# mother_card_20.net
KiCad netlist of a schematic drawn in EAGLE
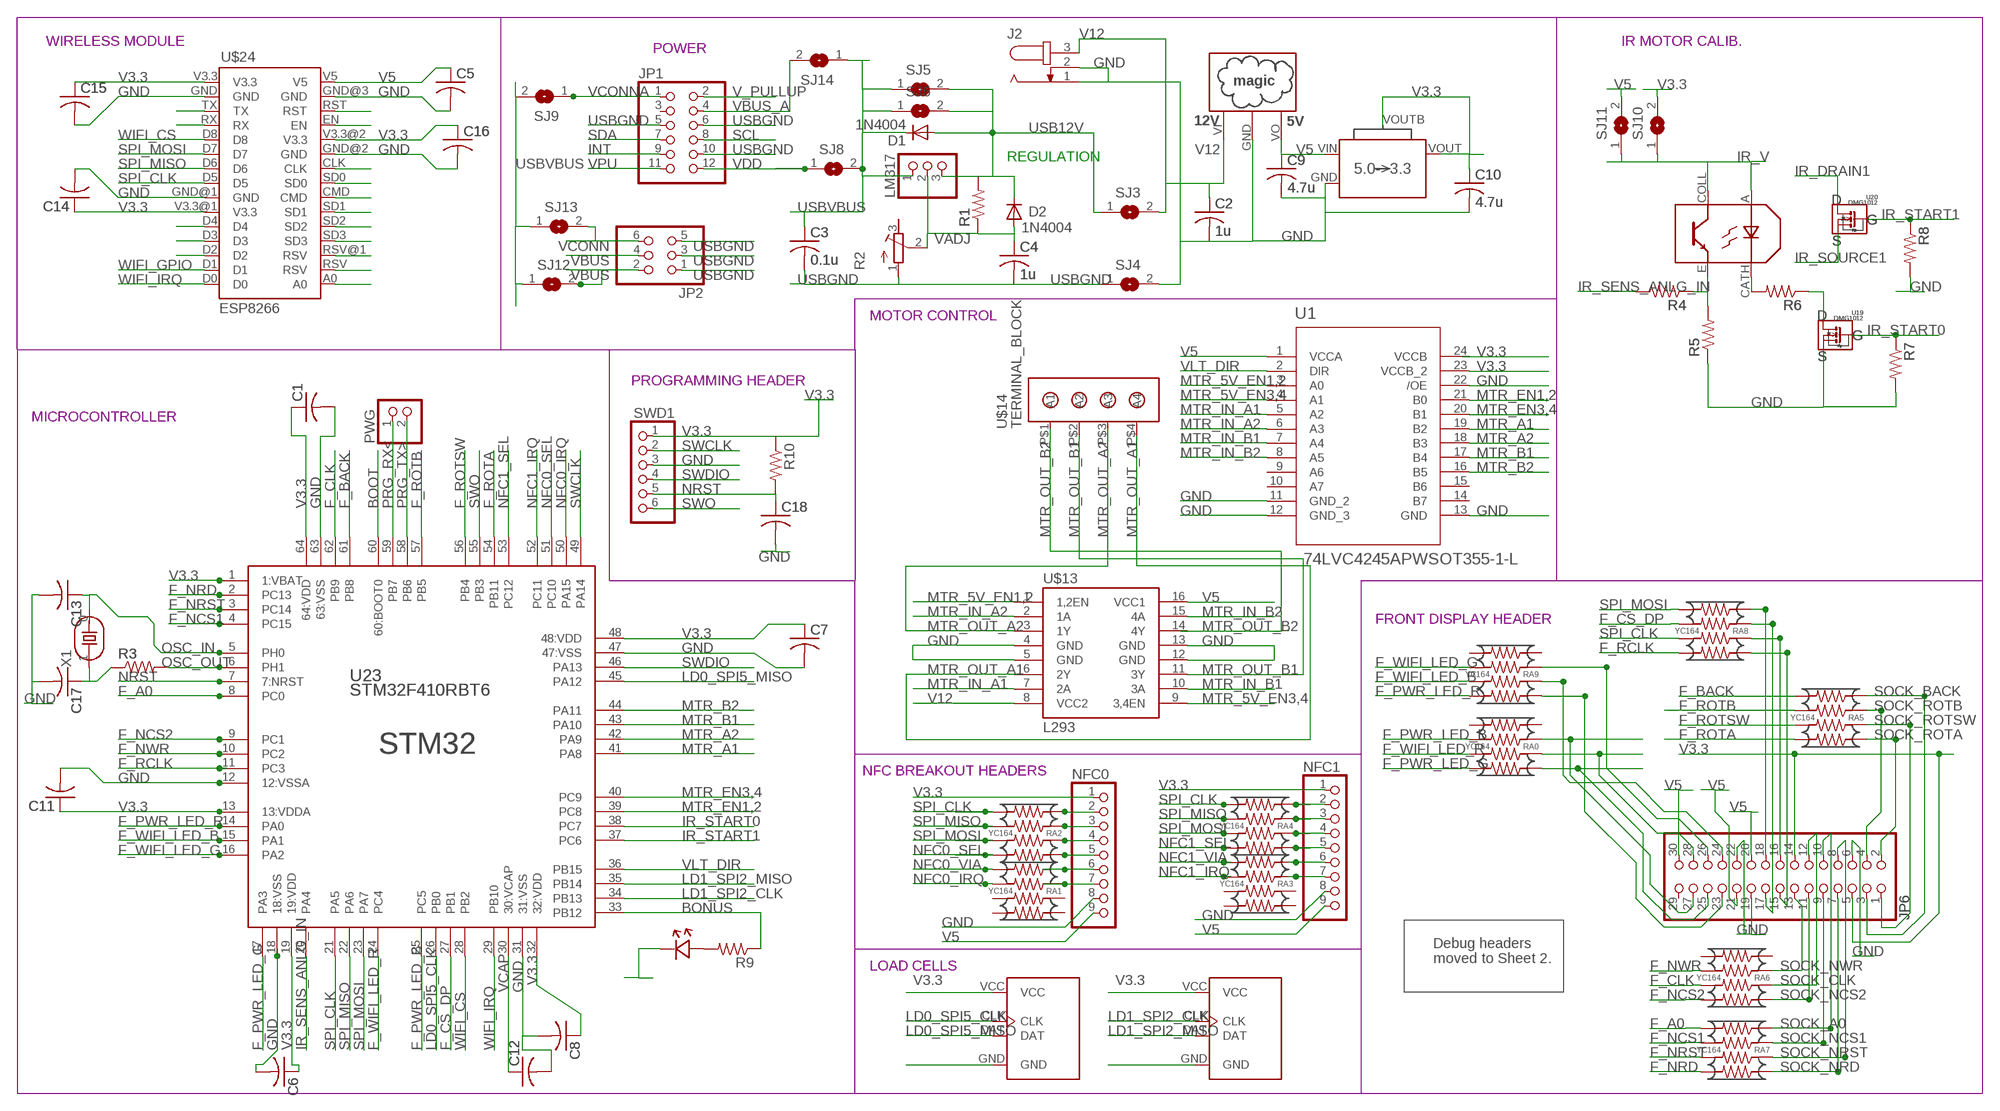
[diagram p0: schematic, sheet 1]
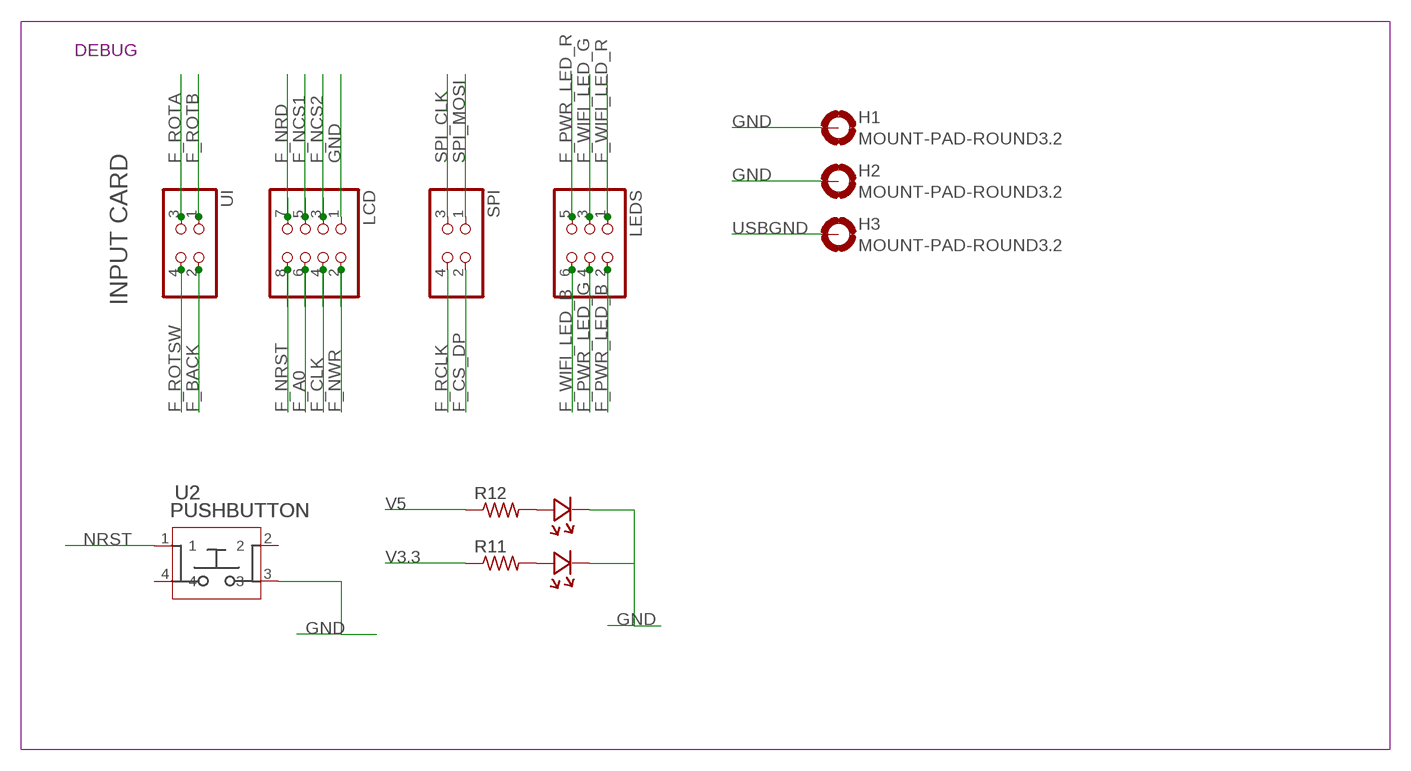
[diagram p1: schematic, sheet 2]

(export (version "E")
  (design (tool "Eeschema 10.0.6"))
  (components
    (comp (ref "H1")
      (value "MOUNT-PAD-ROUND3.2")
      (footprint "eagle-import:3,2-PAD")
      (libsource (lib "eagle-import") (part "MOUNT-PAD-ROUND3.2"))
    )
    (comp (ref "H2")
      (value "MOUNT-PAD-ROUND3.2")
      (footprint "eagle-import:3,2-PAD")
      (libsource (lib "eagle-import") (part "MOUNT-PAD-ROUND3.2"))
    )
    (comp (ref "H3")
      (value "MOUNT-PAD-ROUND3.2")
      (footprint "eagle-import:3,2-PAD")
      (libsource (lib "eagle-import") (part "MOUNT-PAD-ROUND3.2"))
    )
    (comp (ref "LCD")
      (value "PINHD-2X4")
      (footprint "eagle-import:2X04")
      (libsource (lib "eagle-import") (part "PINHD-2X4"))
    )
    (comp (ref "LEDS")
      (value "PINHD-2X3")
      (footprint "eagle-import:2X03")
      (libsource (lib "eagle-import") (part "PINHD-2X3"))
    )
    (comp (ref "R11")
      (value "R-US_R0805")
      (footprint "eagle-import:R0805")
      (libsource (lib "eagle-import") (part "seniorDesign_R-US_R0805"))
    )
    (comp (ref "R12")
      (value "R-US_R0805")
      (footprint "eagle-import:R0805")
      (libsource (lib "eagle-import") (part "seniorDesign_R-US_R0805"))
    )
    (comp (ref "SPI")
      (value "PINHD-2X2")
      (footprint "eagle-import:2X02")
      (libsource (lib "eagle-import") (part "PINHD-2X2"))
    )
    (comp (ref "U$2")
      (value "LED0603")
      (footprint "eagle-import:LED")
      (libsource (lib "eagle-import") (part "LED0603"))
    )
    (comp (ref "U$3")
      (value "LED0603")
      (footprint "eagle-import:LED")
      (libsource (lib "eagle-import") (part "LED0603"))
    )
    (comp (ref "U2")
      (value "PUSHBUTTON")
      (footprint "eagle-import:SWITCH_FSM14JH")
      (fields (field (name "MANUFACTURER_PART_NUMBER") "218259107"))
      (libsource (lib "eagle-import") (part "PUSHBUTTON"))
    )
    (comp (ref "UI")
      (value "PINHD-2X2")
      (footprint "eagle-import:2X02")
      (libsource (lib "eagle-import") (part "PINHD-2X2"))
    )
    (comp (ref "C1")
      (value "C-USC0805")
      (footprint "eagle-import:C0805")
      (libsource (lib "eagle-import") (part "C-USC0805"))
    )
    (comp (ref "C2")
      (value "1u")
      (footprint "eagle-import:C0805")
      (libsource (lib "eagle-import") (part "C-USC0805"))
    )
    (comp (ref "C3")
      (value "0.1u")
      (footprint "eagle-import:C0805")
      (libsource (lib "eagle-import") (part "C-USC0805"))
    )
    (comp (ref "C4")
      (value "1u")
      (footprint "eagle-import:C0805")
      (libsource (lib "eagle-import") (part "C-USC0805"))
    )
    (comp (ref "C5")
      (value "C-USC0805")
      (footprint "eagle-import:C0805")
      (libsource (lib "eagle-import") (part "C-USC0805"))
    )
    (comp (ref "C6")
      (value "C-USC0805")
      (footprint "eagle-import:C0805")
      (libsource (lib "eagle-import") (part "C-USC0805"))
    )
    (comp (ref "C7")
      (value "C-USC0805")
      (footprint "eagle-import:C0805")
      (libsource (lib "eagle-import") (part "C-USC0805"))
    )
    (comp (ref "C8")
      (value "C-USC0805")
      (footprint "eagle-import:C0805")
      (libsource (lib "eagle-import") (part "C-USC0805"))
    )
    (comp (ref "C9")
      (value "4.7u")
      (footprint "eagle-import:C0805")
      (libsource (lib "eagle-import") (part "C-USC0805"))
    )
    (comp (ref "C10")
      (value "4.7u")
      (footprint "eagle-import:C0805")
      (libsource (lib "eagle-import") (part "C-USC0805"))
    )
    (comp (ref "C11")
      (value "C-USC0805")
      (footprint "eagle-import:C0805")
      (libsource (lib "eagle-import") (part "C-USC0805"))
    )
    (comp (ref "C12")
      (value "C-USC0805")
      (footprint "eagle-import:C0805")
      (libsource (lib "eagle-import") (part "C-USC0805"))
    )
    (comp (ref "C13")
      (value "C-USC0603")
      (footprint "eagle-import:C0603")
      (libsource (lib "eagle-import") (part "C-USC0603"))
    )
    (comp (ref "C14")
      (value "C-USC0805")
      (footprint "eagle-import:C0805")
      (libsource (lib "eagle-import") (part "C-USC0805"))
    )
    (comp (ref "C15")
      (value "C-USC0805")
      (footprint "eagle-import:C0805")
      (libsource (lib "eagle-import") (part "C-USC0805"))
    )
    (comp (ref "C16")
      (value "C-USC0805")
      (footprint "eagle-import:C0805")
      (libsource (lib "eagle-import") (part "C-USC0805"))
    )
    (comp (ref "C17")
      (value "C-USC0603")
      (footprint "eagle-import:C0603")
      (libsource (lib "eagle-import") (part "C-USC0603"))
    )
    (comp (ref "C18")
      (value "C-USC0805")
      (footprint "eagle-import:C0805")
      (libsource (lib "eagle-import") (part "C-USC0805"))
    )
    (comp (ref "D1")
      (value "1N4004")
      (footprint "eagle-import:DO41-10")
      (libsource (lib "eagle-import") (part "1N4004"))
    )
    (comp (ref "D2")
      (value "1N4004")
      (footprint "eagle-import:DO41-10")
      (libsource (lib "eagle-import") (part "1N4004"))
    )
    (comp (ref "IRSENS")
      (value "TCRT5000")
      (footprint "eagle-import:TCRT5000")
      (libsource (lib "eagle-import") (part "TCRT5000"))
    )
    (comp (ref "J2")
      (value "JACK-PLUG0")
      (footprint "eagle-import:SPC4077")
      (libsource (lib "eagle-import") (part "JACK-PLUG0"))
    )
    (comp (ref "JP1")
      (value "PINHD-2X6")
      (footprint "eagle-import:2X06")
      (libsource (lib "eagle-import") (part "PINHD-2X6"))
    )
    (comp (ref "JP2")
      (value "PINHD-2X3")
      (footprint "eagle-import:2X03")
      (libsource (lib "eagle-import") (part "PINHD-2X3"))
    )
    (comp (ref "JP6")
      (value "PINHD-2X15/SOCK")
      (footprint "eagle-import:2X15_SOCK")
      (libsource (lib "eagle-import") (part "PINHD-2X15/SOCK"))
    )
    (comp (ref "LM317")
      (value "PINHD-1X3")
      (footprint "eagle-import:1X03")
      (libsource (lib "eagle-import") (part "PINHD-1X3"))
    )
    (comp (ref "NFC0")
      (value "PINHD-1X9")
      (footprint "eagle-import:1X09")
      (libsource (lib "eagle-import") (part "PINHD-1X9"))
    )
    (comp (ref "NFC1")
      (value "PINHD-1X9")
      (footprint "eagle-import:1X09")
      (libsource (lib "eagle-import") (part "PINHD-1X9"))
    )
    (comp (ref "PWG")
      (value "PINHD-1X2")
      (footprint "eagle-import:1X02")
      (libsource (lib "eagle-import") (part "PINHD-1X2"))
    )
    (comp (ref "R1")
      (value "R-US_R0805")
      (footprint "eagle-import:R0805")
      (libsource (lib "eagle-import") (part "seniorDesign_R-US_R0805"))
    )
    (comp (ref "R2")
      (value "R-TRIMM64W")
      (footprint "eagle-import:RTRIM64W")
      (libsource (lib "eagle-import") (part "R-TRIMM64W"))
    )
    (comp (ref "R3")
      (value "R-US_R0805")
      (footprint "eagle-import:R0805")
      (libsource (lib "eagle-import") (part "seniorDesign_R-US_R0805"))
    )
    (comp (ref "R4")
      (value "R-US_R0805")
      (footprint "eagle-import:R0805")
      (libsource (lib "eagle-import") (part "seniorDesign_R-US_R0805"))
    )
    (comp (ref "R5")
      (value "R-US_R0805")
      (footprint "eagle-import:R0805")
      (libsource (lib "eagle-import") (part "seniorDesign_R-US_R0805"))
    )
    (comp (ref "R6")
      (value "R-US_R0805")
      (footprint "eagle-import:R0805")
      (libsource (lib "eagle-import") (part "seniorDesign_R-US_R0805"))
    )
    (comp (ref "R7")
      (value "R-US_R0805")
      (footprint "eagle-import:R0805")
      (libsource (lib "eagle-import") (part "seniorDesign_R-US_R0805"))
    )
    (comp (ref "R8")
      (value "R-US_R0805")
      (footprint "eagle-import:R0805")
      (libsource (lib "eagle-import") (part "seniorDesign_R-US_R0805"))
    )
    (comp (ref "R9")
      (value "R-US_R0805")
      (footprint "eagle-import:R0805")
      (libsource (lib "eagle-import") (part "R-US_R0805"))
    )
    (comp (ref "R10")
      (value "R-US_R0805")
      (footprint "eagle-import:R0805")
      (libsource (lib "eagle-import") (part "R-US_R0805"))
    )
    (comp (ref "RA0")
      (value "YC164")
      (footprint "eagle-import:YC164")
      (libsource (lib "eagle-import") (part "YC164"))
    )
    (comp (ref "RA1")
      (value "YC164")
      (footprint "eagle-import:YC164")
      (libsource (lib "eagle-import") (part "YC164"))
    )
    (comp (ref "RA2")
      (value "YC164")
      (footprint "eagle-import:YC164")
      (libsource (lib "eagle-import") (part "YC164"))
    )
    (comp (ref "RA3")
      (value "YC164")
      (footprint "eagle-import:YC164")
      (libsource (lib "eagle-import") (part "YC164"))
    )
    (comp (ref "RA4")
      (value "YC164")
      (footprint "eagle-import:YC164")
      (libsource (lib "eagle-import") (part "YC164"))
    )
    (comp (ref "RA5")
      (value "YC164")
      (footprint "eagle-import:YC164")
      (libsource (lib "eagle-import") (part "YC164"))
    )
    (comp (ref "RA6")
      (value "YC164")
      (footprint "eagle-import:YC164")
      (libsource (lib "eagle-import") (part "YC164"))
    )
    (comp (ref "RA7")
      (value "YC164")
      (footprint "eagle-import:YC164")
      (libsource (lib "eagle-import") (part "YC164"))
    )
    (comp (ref "RA8")
      (value "YC164")
      (footprint "eagle-import:YC164")
      (libsource (lib "eagle-import") (part "YC164"))
    )
    (comp (ref "RA9")
      (value "YC164")
      (footprint "eagle-import:YC164")
      (libsource (lib "eagle-import") (part "YC164"))
    )
    (comp (ref "SJ3") (value "SJ") (footprint "eagle-import:SJ") (libsource (lib "eagle-import") (part "SJ")))
    (comp (ref "SJ4") (value "SJ") (footprint "eagle-import:SJ") (libsource (lib "eagle-import") (part "SJ")))
    (comp (ref "SJ5") (value "SJ") (footprint "eagle-import:SJ") (libsource (lib "eagle-import") (part "SJ")))
    (comp (ref "SJ6") (value "SJ") (footprint "eagle-import:SJ") (libsource (lib "eagle-import") (part "SJ")))
    (comp (ref "SJ8") (value "SJ") (footprint "eagle-import:SJ") (libsource (lib "eagle-import") (part "SJ")))
    (comp (ref "SJ9") (value "SJ") (footprint "eagle-import:SJ") (libsource (lib "eagle-import") (part "SJ")))
    (comp (ref "SJ10")
      (value "SJ")
      (footprint "eagle-import:SJ")
      (libsource (lib "eagle-import") (part "SJ"))
    )
    (comp (ref "SJ11")
      (value "SJ")
      (footprint "eagle-import:SJ")
      (libsource (lib "eagle-import") (part "SJ"))
    )
    (comp (ref "SJ12")
      (value "SJ")
      (footprint "eagle-import:SJ")
      (libsource (lib "eagle-import") (part "SJ"))
    )
    (comp (ref "SJ13")
      (value "SJ")
      (footprint "eagle-import:SJ")
      (libsource (lib "eagle-import") (part "SJ"))
    )
    (comp (ref "SJ14")
      (value "SJ")
      (footprint "eagle-import:SJ")
      (libsource (lib "eagle-import") (part "SJ"))
    )
    (comp (ref "SWD1")
      (value "PINHD-1X6")
      (footprint "eagle-import:1X06")
      (libsource (lib "eagle-import") (part "PINHD-1X6"))
    )
    (comp (ref "U$1")
      (value "LED0603")
      (footprint "eagle-import:LED")
      (libsource (lib "eagle-import") (part "LED0603"))
    )
    (comp (ref "U$13")
      (value "L293")
      (footprint "eagle-import:DIL16")
      (libsource (lib "eagle-import") (part "L293"))
    )
    (comp (ref "U$14")
      (value "TERMINAL_BLOCK")
      (footprint "eagle-import:1X4_BLOCK")
      (libsource (lib "eagle-import") (part "TERMINAL_BLOCK"))
    )
    (comp (ref "U$15")
      (value "AP2114H")
      (footprint "eagle-import:AP2114H")
      (libsource (lib "eagle-import") (part "AP2114H"))
    )
    (comp (ref "U$16")
      (value "OKI-78SR-W36")
      (footprint "eagle-import:SIP3")
      (libsource (lib "eagle-import") (part "OKI-78SR-W36"))
    )
    (comp (ref "U$21")
      (value "HX711")
      (footprint "eagle-import:HX711")
      (libsource (lib "eagle-import") (part "HX711"))
    )
    (comp (ref "U$22")
      (value "HX711")
      (footprint "eagle-import:HX711")
      (libsource (lib "eagle-import") (part "HX711"))
    )
    (comp (ref "U$24")
      (value "ESP8266")
      (footprint "eagle-import:ESP8266")
      (libsource (lib "eagle-import") (part "ESP8266"))
    )
    (comp (ref "U1")
      (value "74LVC4245APWSOT355-1-L")
      (footprint "eagle-import:SOT355-1-L")
      (fields (field (name "MANUFACTURER_PART_NUMBER") "74LVC4245APW"))
      (libsource (lib "eagle-import") (part "74LVC4245APWSOT355-1-L"))
    )
    (comp (ref "U19")
      (value "DMG1012")
      (footprint "eagle-import:SOT323")
      (libsource (lib "eagle-import") (part "DMG1012"))
    )
    (comp (ref "U20")
      (value "DMG1012")
      (footprint "eagle-import:SOT323")
      (libsource (lib "eagle-import") (part "DMG1012"))
    )
    (comp (ref "U23")
      (value "STM32F410RBT6")
      (footprint "eagle-import:QFP50P1200X1200X160-64N")
      (libsource (lib "eagle-import") (part "STM32F410RBT6"))
    )
    (comp (ref "X1")
      (value "HC-49S_9B")
      (footprint "eagle-import:HC-49S_9B")
      (libsource (lib "eagle-import") (part "HC-49S_9B"))
    )
  )
  (nets
    (net (code "1") (name "BONUS") (class "Default")
      (node (ref "R9") (pin "1") (pinfunction "1_1") (pintype "passive"))
      (node (ref "U23") (pin "33") (pinfunction "PB12_33") (pintype "bidirectional"))
    )
    (net (code "2") (name "BOOT") (class "Default")
      (node (ref "U23") (pin "60") (pinfunction "60:BOOT0_60") (pintype "bidirectional"))
    )
    (net (code "3") (name "F_A0") (class "Default")
      (node (ref "LCD") (pin "6") (pinfunction "6_6") (pintype "passive"))
      (node (ref "RA7") (pin "P$4") (pinfunction "4_P$4") (pintype "passive"))
      (node (ref "U23") (pin "8") (pinfunction "PC0_8") (pintype "bidirectional"))
    )
    (net (code "4") (name "F_BACK") (class "Default")
      (node (ref "RA5") (pin "P$4") (pinfunction "4_P$4") (pintype "passive"))
      (node (ref "U23") (pin "61") (pinfunction "PB8_61") (pintype "bidirectional"))
      (node (ref "UI") (pin "2") (pinfunction "2_2") (pintype "passive"))
    )
    (net (code "5") (name "F_CLK") (class "Default")
      (node (ref "LCD") (pin "4") (pinfunction "4_4") (pintype "passive"))
      (node (ref "RA6") (pin "P$2") (pinfunction "2_P$2") (pintype "passive"))
      (node (ref "U23") (pin "62") (pinfunction "PB9_62") (pintype "bidirectional"))
    )
    (net (code "6") (name "F_CS_DP") (class "Default")
      (node (ref "RA8") (pin "P$3") (pinfunction "3_P$3") (pintype "passive"))
      (node (ref "SPI") (pin "2") (pinfunction "2_2") (pintype "passive"))
      (node (ref "U23") (pin "27") (pinfunction "PB1_27") (pintype "bidirectional"))
    )
    (net (code "7") (name "F_NCS1") (class "Default")
      (node (ref "LCD") (pin "5") (pinfunction "5_5") (pintype "passive"))
      (node (ref "RA7") (pin "P$3") (pinfunction "3_P$3") (pintype "passive"))
      (node (ref "U23") (pin "4") (pinfunction "PC15_4") (pintype "bidirectional"))
    )
    (net (code "8") (name "F_NCS2") (class "Default")
      (node (ref "LCD") (pin "3") (pinfunction "3_3") (pintype "passive"))
      (node (ref "RA6") (pin "P$1") (pinfunction "1_P$1") (pintype "passive"))
      (node (ref "U23") (pin "9") (pinfunction "PC1_9") (pintype "bidirectional"))
    )
    (net (code "9") (name "F_NRD") (class "Default")
      (node (ref "LCD") (pin "7") (pinfunction "7_7") (pintype "passive"))
      (node (ref "RA7") (pin "P$1") (pinfunction "1_P$1") (pintype "passive"))
      (node (ref "U23") (pin "2") (pinfunction "PC13_2") (pintype "bidirectional"))
    )
    (net (code "10") (name "F_NRST") (class "Default")
      (node (ref "LCD") (pin "8") (pinfunction "8_8") (pintype "passive"))
      (node (ref "RA7") (pin "P$2") (pinfunction "2_P$2") (pintype "passive"))
      (node (ref "U23") (pin "3") (pinfunction "PC14_3") (pintype "bidirectional"))
    )
    (net (code "11") (name "F_NWR") (class "Default")
      (node (ref "LCD") (pin "2") (pinfunction "2_2") (pintype "passive"))
      (node (ref "RA6") (pin "P$3") (pinfunction "3_P$3") (pintype "passive"))
      (node (ref "U23") (pin "10") (pinfunction "PC2_10") (pintype "bidirectional"))
    )
    (net (code "12") (name "F_PWR_LED_B") (class "Default")
      (node (ref "LEDS") (pin "2") (pinfunction "2_2") (pintype "passive"))
      (node (ref "RA0") (pin "P$3") (pinfunction "3_P$3") (pintype "passive"))
      (node (ref "U23") (pin "25") (pinfunction "PC5_25") (pintype "bidirectional"))
    )
    (net (code "13") (name "F_PWR_LED_G") (class "Default")
      (node (ref "LEDS") (pin "4") (pinfunction "4_4") (pintype "passive"))
      (node (ref "RA0") (pin "P$1") (pinfunction "1_P$1") (pintype "passive"))
      (node (ref "U23") (pin "17") (pinfunction "PA3_17") (pintype "bidirectional"))
    )
    (net (code "14") (name "F_PWR_LED_R") (class "Default")
      (node (ref "LEDS") (pin "5") (pinfunction "5_5") (pintype "passive"))
      (node (ref "RA9") (pin "P$1") (pinfunction "1_P$1") (pintype "passive"))
      (node (ref "U23") (pin "14") (pinfunction "PA0_14") (pintype "bidirectional"))
    )
    (net (code "15") (name "F_RCLK") (class "Default")
      (node (ref "RA8") (pin "P$1") (pinfunction "1_P$1") (pintype "passive"))
      (node (ref "SPI") (pin "4") (pinfunction "4_4") (pintype "passive"))
      (node (ref "U23") (pin "11") (pinfunction "PC3_11") (pintype "bidirectional"))
    )
    (net (code "16") (name "F_ROTA") (class "Default")
      (node (ref "RA5") (pin "P$1") (pinfunction "1_P$1") (pintype "passive"))
      (node (ref "U23") (pin "54") (pinfunction "PB11_54") (pintype "bidirectional"))
      (node (ref "UI") (pin "3") (pinfunction "3_3") (pintype "passive"))
    )
    (net (code "17") (name "F_ROTB") (class "Default")
      (node (ref "RA5") (pin "P$3") (pinfunction "3_P$3") (pintype "passive"))
      (node (ref "U23") (pin "57") (pinfunction "PB5_57") (pintype "bidirectional"))
      (node (ref "UI") (pin "1") (pinfunction "1_1") (pintype "passive"))
    )
    (net (code "18") (name "F_ROTSW") (class "Default")
      (node (ref "RA5") (pin "P$2") (pinfunction "2_P$2") (pintype "passive"))
      (node (ref "U23") (pin "56") (pinfunction "PB4_56") (pintype "bidirectional"))
      (node (ref "UI") (pin "4") (pinfunction "4_4") (pintype "passive"))
    )
    (net (code "19") (name "F_WIFI_LED_B") (class "Default")
      (node (ref "LEDS") (pin "6") (pinfunction "6_6") (pintype "passive"))
      (node (ref "RA9") (pin "P$2") (pinfunction "2_P$2") (pintype "passive"))
      (node (ref "U23") (pin "15") (pinfunction "PA1_15") (pintype "bidirectional"))
    )
    (net (code "20") (name "F_WIFI_LED_G") (class "Default")
      (node (ref "LEDS") (pin "3") (pinfunction "3_3") (pintype "passive"))
      (node (ref "RA9") (pin "P$3") (pinfunction "3_P$3") (pintype "passive"))
      (node (ref "U23") (pin "16") (pinfunction "PA2_16") (pintype "bidirectional"))
    )
    (net (code "21") (name "F_WIFI_LED_R") (class "Default")
      (node (ref "LEDS") (pin "1") (pinfunction "1_1") (pintype "passive"))
      (node (ref "RA0") (pin "P$2") (pinfunction "2_P$2") (pintype "passive"))
      (node (ref "U23") (pin "24") (pinfunction "PC4_24") (pintype "bidirectional"))
    )
    (net (code "22") (name "GND") (class "Default")
      (node (ref "C1") (pin "2") (pinfunction "2_2") (pintype "passive"))
      (node (ref "C10") (pin "2") (pinfunction "2_2") (pintype "passive"))
      (node (ref "C11") (pin "2") (pinfunction "2_2") (pintype "passive"))
      (node (ref "C12") (pin "2") (pinfunction "2_2") (pintype "passive"))
      (node (ref "C13") (pin "2") (pinfunction "2_2") (pintype "passive"))
      (node (ref "C14") (pin "2") (pinfunction "2_2") (pintype "passive"))
      (node (ref "C15") (pin "2") (pinfunction "2_2") (pintype "passive"))
      (node (ref "C16") (pin "2") (pinfunction "2_2") (pintype "passive"))
      (node (ref "C17") (pin "2") (pinfunction "2_2") (pintype "passive"))
      (node (ref "C18") (pin "2") (pinfunction "2_2") (pintype "passive"))
      (node (ref "C2") (pin "2") (pinfunction "2_2") (pintype "passive"))
      (node (ref "C5") (pin "2") (pinfunction "2_2") (pintype "passive"))
      (node (ref "C6") (pin "2") (pinfunction "2_2") (pintype "passive"))
      (node (ref "C7") (pin "2") (pinfunction "2_2") (pintype "passive"))
      (node (ref "C8") (pin "2") (pinfunction "2_2") (pintype "passive"))
      (node (ref "C9") (pin "2") (pinfunction "2_2") (pintype "passive"))
      (node (ref "H1") (pin "B3,2") (pinfunction "MOUNT_B3,2") (pintype "passive"))
      (node (ref "H2") (pin "B3,2") (pinfunction "MOUNT_B3,2") (pintype "passive"))
      (node (ref "J2") (pin "1") (pinfunction "1_1") (pintype "passive"))
      (node (ref "J2") (pin "2") (pinfunction "2_2") (pintype "passive"))
      (node (ref "JP6") (pin "19") (pinfunction "19_19") (pintype "passive"))
      (node (ref "JP6") (pin "22") (pinfunction "22_22") (pintype "passive"))
      (node (ref "JP6") (pin "6") (pinfunction "6_6") (pintype "passive"))
      (node (ref "LCD") (pin "1") (pinfunction "1_1") (pintype "passive"))
      (node (ref "NFC0") (pin "8") (pinfunction "8_8") (pintype "passive"))
      (node (ref "NFC1") (pin "8") (pinfunction "8_8") (pintype "passive"))
      (node (ref "R5") (pin "1") (pinfunction "1_1") (pintype "passive"))
      (node (ref "R7") (pin "2") (pinfunction "2_2") (pintype "passive"))
      (node (ref "R8") (pin "2") (pinfunction "2_2") (pintype "passive"))
      (node (ref "SJ4") (pin "2") (pinfunction "2_2") (pintype "passive"))
      (node (ref "SWD1") (pin "3") (pinfunction "3_3") (pintype "passive"))
      (node (ref "U$13") (pin "12") (pinfunction "GND_12") (pintype "bidirectional"))
      (node (ref "U$13") (pin "13") (pinfunction "GND_13") (pintype "bidirectional"))
      (node (ref "U$13") (pin "4") (pinfunction "GND_4") (pintype "bidirectional"))
      (node (ref "U$13") (pin "5") (pinfunction "GND_5") (pintype "bidirectional"))
      (node (ref "U$15") (pin "GND") (pinfunction "GND_GND") (pintype "power_in"))
      (node (ref "U$16") (pin "GND") (pinfunction "P$2_GND") (pintype "power_in"))
      (node (ref "U$2") (pin "CATHODE") (pinfunction "CA_CATHODE") (pintype "output"))
      (node (ref "U$21") (pin "GND") (pinfunction "GND_GND") (pintype "power_in"))
      (node (ref "U$22") (pin "GND") (pinfunction "GND_GND") (pintype "power_in"))
      (node (ref "U$24") (pin "GND") (pinfunction "GND_GND") (pintype "bidirectional"))
      (node (ref "U$24") (pin "GND@1") (pinfunction "GND_GND@1") (pintype "bidirectional"))
      (node (ref "U$24") (pin "GND@2") (pinfunction "GND_GND@2") (pintype "bidirectional"))
      (node (ref "U$24") (pin "GND@3") (pinfunction "GND_GND@3") (pintype "bidirectional"))
      (node (ref "U$3") (pin "CATHODE") (pinfunction "CA_CATHODE") (pintype "output"))
      (node (ref "U1") (pin "11") (pinfunction "GND_2_11") (pintype "power_in"))
      (node (ref "U1") (pin "12") (pinfunction "GND_3_12") (pintype "power_in"))
      (node (ref "U1") (pin "13") (pinfunction "GND_13") (pintype "power_in"))
      (node (ref "U1") (pin "22") (pinfunction "/OE_22") (pintype "input"))
      (node (ref "U19") (pin "S") (pinfunction "S_S") (pintype "bidirectional"))
      (node (ref "U2") (pin "3") (pinfunction "3_3") (pintype "passive"))
      (node (ref "U23") (pin "12") (pinfunction "12:VSSA_12") (pintype "bidirectional"))
      (node (ref "U23") (pin "18") (pinfunction "18:VSS_18") (pintype "bidirectional"))
      (node (ref "U23") (pin "31") (pinfunction "31:VSS_31") (pintype "bidirectional"))
      (node (ref "U23") (pin "47") (pinfunction "47:VSS_47") (pintype "bidirectional"))
      (node (ref "U23") (pin "63") (pinfunction "63:VSS_63") (pintype "bidirectional"))
    )
    (net (code "23") (name "INT") (class "Default")
      (node (ref "JP1") (pin "9") (pinfunction "9_9") (pintype "passive"))
    )
    (net (code "24") (name "IR_DRAIN1") (class "Default")
      (node (ref "U20") (pin "D") (pinfunction "D_D") (pintype "bidirectional"))
    )
    (net (code "25") (name "IR_SENS_ANLG_IN") (class "Default")
      (node (ref "R4") (pin "2") (pinfunction "2_2") (pintype "passive"))
      (node (ref "U23") (pin "20") (pinfunction "PA4_20") (pintype "bidirectional"))
    )
    (net (code "26") (name "IR_SOURCE1") (class "Default")
      (node (ref "U20") (pin "S") (pinfunction "S_S") (pintype "bidirectional"))
    )
    (net (code "27") (name "IR_START0") (class "Default")
      (node (ref "R7") (pin "1") (pinfunction "1_1") (pintype "passive"))
      (node (ref "U19") (pin "G") (pinfunction "G_G") (pintype "bidirectional"))
      (node (ref "U23") (pin "38") (pinfunction "PC7_38") (pintype "bidirectional"))
    )
    (net (code "28") (name "IR_START1") (class "Default")
      (node (ref "R8") (pin "1") (pinfunction "1_1") (pintype "passive"))
      (node (ref "U20") (pin "G") (pinfunction "G_G") (pintype "bidirectional"))
      (node (ref "U23") (pin "37") (pinfunction "PC6_37") (pintype "bidirectional"))
    )
    (net (code "29") (name "IR_V") (class "Default")
      (node (ref "IRSENS") (pin "A") (pinfunction "A_A") (pintype "bidirectional"))
      (node (ref "IRSENS") (pin "COLL") (pinfunction "COLL_COLL") (pintype "bidirectional"))
      (node (ref "SJ10") (pin "1") (pinfunction "1_1") (pintype "passive"))
      (node (ref "SJ11") (pin "1") (pinfunction "1_1") (pintype "passive"))
    )
    (net (code "30") (name "LD0_SPI5_CLK") (class "Default")
      (node (ref "U$21") (pin "CLK") (pinfunction "CLK_CLK") (pintype "bidirectional"))
      (node (ref "U23") (pin "26") (pinfunction "PB0_26") (pintype "bidirectional"))
    )
    (net (code "31") (name "LD0_SPI5_MISO") (class "Default")
      (node (ref "U$21") (pin "DAT") (pinfunction "DAT_DAT") (pintype "bidirectional"))
      (node (ref "U23") (pin "45") (pinfunction "PA12_45") (pintype "bidirectional"))
    )
    (net (code "32") (name "LD1_SPI2_CLK") (class "Default")
      (node (ref "U$22") (pin "CLK") (pinfunction "CLK_CLK") (pintype "bidirectional"))
      (node (ref "U23") (pin "34") (pinfunction "PB13_34") (pintype "bidirectional"))
    )
    (net (code "33") (name "LD1_SPI2_MISO") (class "Default")
      (node (ref "U$22") (pin "DAT") (pinfunction "DAT_DAT") (pintype "bidirectional"))
      (node (ref "U23") (pin "35") (pinfunction "PB14_35") (pintype "bidirectional"))
    )
    (net (code "34") (name "MTR_5V_EN1,2") (class "Default")
      (node (ref "U$13") (pin "1") (pinfunction "1,2EN_1") (pintype "bidirectional"))
      (node (ref "U1") (pin "3") (pinfunction "A0_3") (pintype "bidirectional"))
    )
    (net (code "35") (name "MTR_5V_EN3,4") (class "Default")
      (node (ref "U$13") (pin "9") (pinfunction "3,4EN_9") (pintype "bidirectional"))
      (node (ref "U1") (pin "4") (pinfunction "A1_4") (pintype "bidirectional"))
    )
    (net (code "36") (name "MTR_A1") (class "Default")
      (node (ref "U1") (pin "19") (pinfunction "B2_19") (pintype "bidirectional"))
      (node (ref "U23") (pin "41") (pinfunction "PA8_41") (pintype "bidirectional"))
    )
    (net (code "37") (name "MTR_A2") (class "Default")
      (node (ref "U1") (pin "18") (pinfunction "B3_18") (pintype "bidirectional"))
      (node (ref "U23") (pin "42") (pinfunction "PA9_42") (pintype "bidirectional"))
    )
    (net (code "38") (name "MTR_B1") (class "Default")
      (node (ref "U1") (pin "17") (pinfunction "B4_17") (pintype "bidirectional"))
      (node (ref "U23") (pin "43") (pinfunction "PA10_43") (pintype "bidirectional"))
    )
    (net (code "39") (name "MTR_B2") (class "Default")
      (node (ref "U1") (pin "16") (pinfunction "B5_16") (pintype "bidirectional"))
      (node (ref "U23") (pin "44") (pinfunction "PA11_44") (pintype "bidirectional"))
    )
    (net (code "40") (name "MTR_EN1,2") (class "Default")
      (node (ref "U1") (pin "21") (pinfunction "B0_21") (pintype "bidirectional"))
      (node (ref "U23") (pin "39") (pinfunction "PC8_39") (pintype "bidirectional"))
    )
    (net (code "41") (name "MTR_EN3,4") (class "Default")
      (node (ref "U1") (pin "20") (pinfunction "B1_20") (pintype "bidirectional"))
      (node (ref "U23") (pin "40") (pinfunction "PC9_40") (pintype "bidirectional"))
    )
    (net (code "42") (name "MTR_IN_A1") (class "Default")
      (node (ref "U$13") (pin "7") (pinfunction "2A_7") (pintype "bidirectional"))
      (node (ref "U1") (pin "5") (pinfunction "A2_5") (pintype "bidirectional"))
    )
    (net (code "43") (name "MTR_IN_A2") (class "Default")
      (node (ref "U$13") (pin "2") (pinfunction "1A_2") (pintype "bidirectional"))
      (node (ref "U1") (pin "6") (pinfunction "A3_6") (pintype "bidirectional"))
    )
    (net (code "44") (name "MTR_IN_B1") (class "Default")
      (node (ref "U$13") (pin "10") (pinfunction "3A_10") (pintype "bidirectional"))
      (node (ref "U1") (pin "7") (pinfunction "A4_7") (pintype "bidirectional"))
    )
    (net (code "45") (name "MTR_IN_B2") (class "Default")
      (node (ref "U$13") (pin "15") (pinfunction "4A_15") (pintype "bidirectional"))
      (node (ref "U1") (pin "8") (pinfunction "A5_8") (pintype "bidirectional"))
    )
    (net (code "46") (name "MTR_OUT_A1") (class "Default")
      (node (ref "U$13") (pin "6") (pinfunction "2Y_6") (pintype "bidirectional"))
      (node (ref "U$14") (pin "P$4") (pinfunction "A4_P$4") (pintype "bidirectional"))
    )
    (net (code "47") (name "MTR_OUT_A2") (class "Default")
      (node (ref "U$13") (pin "3") (pinfunction "1Y_3") (pintype "bidirectional"))
      (node (ref "U$14") (pin "P$3") (pinfunction "A3_P$3") (pintype "bidirectional"))
    )
    (net (code "48") (name "MTR_OUT_B1") (class "Default")
      (node (ref "U$13") (pin "11") (pinfunction "3Y_11") (pintype "bidirectional"))
      (node (ref "U$14") (pin "P$2") (pinfunction "A2_P$2") (pintype "bidirectional"))
    )
    (net (code "49") (name "MTR_OUT_B2") (class "Default")
      (node (ref "U$13") (pin "14") (pinfunction "4Y_14") (pintype "bidirectional"))
      (node (ref "U$14") (pin "P$1") (pinfunction "A1_P$1") (pintype "bidirectional"))
    )
    (net (code "50") (name "NFC0_IRQ") (class "Default")
      (node (ref "RA1") (pin "P$3") (pinfunction "3_P$3") (pintype "passive"))
      (node (ref "U23") (pin "50") (pinfunction "PA15_50") (pintype "bidirectional"))
    )
    (net (code "51") (name "NFC0_SEL") (class "Default")
      (node (ref "RA2") (pin "P$1") (pinfunction "1_P$1") (pintype "passive"))
      (node (ref "U23") (pin "51") (pinfunction "PC10_51") (pintype "bidirectional"))
    )
    (net (code "52") (name "NFC0_VIA") (class "Default")
      (node (ref "RA1") (pin "P$4") (pinfunction "4_P$4") (pintype "passive"))
    )
    (net (code "53") (name "NFC1_IRQ") (class "Default")
      (node (ref "RA3") (pin "P$3") (pinfunction "3_P$3") (pintype "passive"))
      (node (ref "U23") (pin "52") (pinfunction "PC11_52") (pintype "bidirectional"))
    )
    (net (code "54") (name "NFC1_SEL") (class "Default")
      (node (ref "RA4") (pin "P$1") (pinfunction "1_P$1") (pintype "passive"))
      (node (ref "U23") (pin "53") (pinfunction "PC12_53") (pintype "bidirectional"))
    )
    (net (code "55") (name "NFC1_VIA") (class "Default")
      (node (ref "RA3") (pin "P$4") (pinfunction "4_P$4") (pintype "passive"))
    )
    (net (code "56") (name "NRST") (class "Default")
      (node (ref "C18") (pin "1") (pinfunction "1_1") (pintype "passive"))
      (node (ref "R10") (pin "2") (pinfunction "2_2") (pintype "passive"))
      (node (ref "SWD1") (pin "5") (pinfunction "5_5") (pintype "passive"))
      (node (ref "U2") (pin "1") (pinfunction "1_1") (pintype "passive"))
      (node (ref "U23") (pin "7") (pinfunction "7:NRST_7") (pintype "bidirectional"))
    )
    (net (code "57") (name "Net-(IRSENS-PadCATH)") (class "Default")
      (node (ref "IRSENS") (pin "CATH") (pinfunction "CATH_CATH") (pintype "bidirectional"))
      (node (ref "R6") (pin "2") (pinfunction "2_2") (pintype "passive"))
    )
    (net (code "58") (name "Net-(IRSENS-PadE)") (class "Default")
      (node (ref "IRSENS") (pin "E") (pinfunction "E_E") (pintype "bidirectional"))
      (node (ref "R4") (pin "1") (pinfunction "1_1") (pintype "passive"))
      (node (ref "R5") (pin "2") (pinfunction "2_2") (pintype "passive"))
    )
    (net (code "59") (name "Net-(R6-Pad1)") (class "Default")
      (node (ref "R6") (pin "1") (pinfunction "1_1") (pintype "passive"))
      (node (ref "U19") (pin "D") (pinfunction "D_D") (pintype "bidirectional"))
    )
    (net (code "60") (name "Net-(RA0-11)") (class "Default")
      (node (ref "JP6") (pin "25") (pinfunction "25_25") (pintype "passive"))
      (node (ref "RA0") (pin "P$11") (pinfunction "11_P$11") (pintype "passive"))
    )
    (net (code "61") (name "Net-(RA0-22)") (class "Default")
      (node (ref "JP6") (pin "28") (pinfunction "28_28") (pintype "passive"))
      (node (ref "RA0") (pin "P$22") (pinfunction "22_P$22") (pintype "passive"))
    )
    (net (code "62") (name "Net-(RA0-33)") (class "Default")
      (node (ref "JP6") (pin "27") (pinfunction "27_27") (pintype "passive"))
      (node (ref "RA0") (pin "P$33") (pinfunction "33_P$33") (pintype "passive"))
    )
    (net (code "63") (name "Net-(RA1-33)") (class "Default")
      (node (ref "NFC0") (pin "7") (pinfunction "7_7") (pintype "passive"))
      (node (ref "RA1") (pin "P$33") (pinfunction "33_P$33") (pintype "passive"))
    )
    (net (code "64") (name "Net-(RA1-44)") (class "Default")
      (node (ref "NFC0") (pin "6") (pinfunction "6_6") (pintype "passive"))
      (node (ref "RA1") (pin "P$44") (pinfunction "44_P$44") (pintype "passive"))
    )
    (net (code "65") (name "Net-(RA2-11)") (class "Default")
      (node (ref "NFC0") (pin "5") (pinfunction "5_5") (pintype "passive"))
      (node (ref "RA2") (pin "P$11") (pinfunction "11_P$11") (pintype "passive"))
    )
    (net (code "66") (name "Net-(RA2-22)") (class "Default")
      (node (ref "NFC0") (pin "4") (pinfunction "4_4") (pintype "passive"))
      (node (ref "RA2") (pin "P$22") (pinfunction "22_P$22") (pintype "passive"))
    )
    (net (code "67") (name "Net-(RA2-33)") (class "Default")
      (node (ref "NFC0") (pin "3") (pinfunction "3_3") (pintype "passive"))
      (node (ref "RA2") (pin "P$33") (pinfunction "33_P$33") (pintype "passive"))
    )
    (net (code "68") (name "Net-(RA2-44)") (class "Default")
      (node (ref "NFC0") (pin "2") (pinfunction "2_2") (pintype "passive"))
      (node (ref "RA2") (pin "P$44") (pinfunction "44_P$44") (pintype "passive"))
    )
    (net (code "69") (name "Net-(RA3-33)") (class "Default")
      (node (ref "NFC1") (pin "7") (pinfunction "7_7") (pintype "passive"))
      (node (ref "RA3") (pin "P$33") (pinfunction "33_P$33") (pintype "passive"))
    )
    (net (code "70") (name "Net-(RA3-44)") (class "Default")
      (node (ref "NFC1") (pin "6") (pinfunction "6_6") (pintype "passive"))
      (node (ref "RA3") (pin "P$44") (pinfunction "44_P$44") (pintype "passive"))
    )
    (net (code "71") (name "Net-(RA4-11)") (class "Default")
      (node (ref "NFC1") (pin "5") (pinfunction "5_5") (pintype "passive"))
      (node (ref "RA4") (pin "P$11") (pinfunction "11_P$11") (pintype "passive"))
    )
    (net (code "72") (name "Net-(RA4-22)") (class "Default")
      (node (ref "NFC1") (pin "4") (pinfunction "4_4") (pintype "passive"))
      (node (ref "RA4") (pin "P$22") (pinfunction "22_P$22") (pintype "passive"))
    )
    (net (code "73") (name "Net-(RA4-33)") (class "Default")
      (node (ref "NFC1") (pin "3") (pinfunction "3_3") (pintype "passive"))
      (node (ref "RA4") (pin "P$33") (pinfunction "33_P$33") (pintype "passive"))
    )
    (net (code "74") (name "Net-(RA4-44)") (class "Default")
      (node (ref "NFC1") (pin "2") (pinfunction "2_2") (pintype "passive"))
      (node (ref "RA4") (pin "P$44") (pinfunction "44_P$44") (pintype "passive"))
    )
    (net (code "75") (name "Net-(RA8-11)") (class "Default")
      (node (ref "JP6") (pin "15") (pinfunction "15_15") (pintype "passive"))
      (node (ref "RA8") (pin "P$11") (pinfunction "11_P$11") (pintype "passive"))
    )
    (net (code "76") (name "Net-(RA8-22)") (class "Default")
      (node (ref "JP6") (pin "16") (pinfunction "16_16") (pintype "passive"))
      (node (ref "RA8") (pin "P$22") (pinfunction "22_P$22") (pintype "passive"))
    )
    (net (code "77") (name "Net-(RA8-33)") (class "Default")
      (node (ref "JP6") (pin "17") (pinfunction "17_17") (pintype "passive"))
      (node (ref "RA8") (pin "P$33") (pinfunction "33_P$33") (pintype "passive"))
    )
    (net (code "78") (name "Net-(RA8-44)") (class "Default")
      (node (ref "JP6") (pin "18") (pinfunction "18_18") (pintype "passive"))
      (node (ref "RA8") (pin "P$44") (pinfunction "44_P$44") (pintype "passive"))
    )
    (net (code "79") (name "Net-(RA9-11)") (class "Default")
      (node (ref "JP6") (pin "23") (pinfunction "23_23") (pintype "passive"))
      (node (ref "RA9") (pin "P$11") (pinfunction "11_P$11") (pintype "passive"))
    )
    (net (code "80") (name "Net-(RA9-22)") (class "Default")
      (node (ref "JP6") (pin "24") (pinfunction "24_24") (pintype "passive"))
      (node (ref "RA9") (pin "P$22") (pinfunction "22_P$22") (pintype "passive"))
    )
    (net (code "81") (name "Net-(RA9-33)") (class "Default")
      (node (ref "JP6") (pin "26") (pinfunction "26_26") (pintype "passive"))
      (node (ref "RA9") (pin "P$33") (pinfunction "33_P$33") (pintype "passive"))
    )
    (net (code "82") (name "Net-(U$1-AN)") (class "Default")
      (node (ref "R9") (pin "2") (pinfunction "2_2") (pintype "passive"))
      (node (ref "U$1") (pin "ANODE") (pinfunction "AN_ANODE") (pintype "input"))
    )
    (net (code "83") (name "Net-(U$2-AN)") (class "Default")
      (node (ref "R11") (pin "2") (pinfunction "2_2") (pintype "passive"))
      (node (ref "U$2") (pin "ANODE") (pinfunction "AN_ANODE") (pintype "input"))
    )
    (net (code "84") (name "Net-(U$3-AN)") (class "Default")
      (node (ref "R12") (pin "2") (pinfunction "2_2") (pintype "passive"))
      (node (ref "U$3") (pin "ANODE") (pinfunction "AN_ANODE") (pintype "input"))
    )
    (net (code "85") (name "Net-(U23-PH1)") (class "Default")
      (node (ref "R3") (pin "2") (pinfunction "2_2") (pintype "passive"))
      (node (ref "U23") (pin "6") (pinfunction "PH1_6") (pintype "bidirectional"))
    )
    (net (code "86") (name "OSC_IN") (class "Default")
      (node (ref "C13") (pin "1") (pinfunction "1_1") (pintype "passive"))
      (node (ref "U23") (pin "5") (pinfunction "PH0_5") (pintype "bidirectional"))
      (node (ref "X1") (pin "0") (pinfunction "P$1_0") (pintype "bidirectional"))
    )
    (net (code "87") (name "OSC_OUT") (class "Default")
      (node (ref "C17") (pin "1") (pinfunction "1_1") (pintype "passive"))
      (node (ref "R3") (pin "1") (pinfunction "1_1") (pintype "passive"))
      (node (ref "X1") (pin "1") (pinfunction "P$2_1") (pintype "bidirectional"))
    )
    (net (code "88") (name "PRG_RX<") (class "Default")
      (node (ref "PWG") (pin "1") (pinfunction "1_1") (pintype "passive"))
      (node (ref "U23") (pin "59") (pinfunction "PB7_59") (pintype "bidirectional"))
    )
    (net (code "89") (name "PRG_TX>") (class "Default")
      (node (ref "PWG") (pin "2") (pinfunction "2_2") (pintype "passive"))
      (node (ref "U23") (pin "58") (pinfunction "PB6_58") (pintype "bidirectional"))
    )
    (net (code "90") (name "SCL") (class "Default")
      (node (ref "JP1") (pin "8") (pinfunction "8_8") (pintype "passive"))
    )
    (net (code "91") (name "SDA") (class "Default")
      (node (ref "JP1") (pin "7") (pinfunction "7_7") (pintype "passive"))
    )
    (net (code "92") (name "SOCK_A0") (class "Default")
      (node (ref "JP6") (pin "10") (pinfunction "10_10") (pintype "passive"))
      (node (ref "RA7") (pin "P$44") (pinfunction "44_P$44") (pintype "passive"))
    )
    (net (code "93") (name "SOCK_BACK") (class "Default")
      (node (ref "JP6") (pin "3") (pinfunction "3_3") (pintype "passive"))
      (node (ref "RA5") (pin "P$44") (pinfunction "44_P$44") (pintype "passive"))
    )
    (net (code "94") (name "SOCK_CLK") (class "Default")
      (node (ref "JP6") (pin "12") (pinfunction "12_12") (pintype "passive"))
      (node (ref "RA6") (pin "P$22") (pinfunction "22_P$22") (pintype "passive"))
    )
    (net (code "95") (name "SOCK_NCS1") (class "Default")
      (node (ref "JP6") (pin "9") (pinfunction "9_9") (pintype "passive"))
      (node (ref "RA7") (pin "P$33") (pinfunction "33_P$33") (pintype "passive"))
    )
    (net (code "96") (name "SOCK_NCS2") (class "Default")
      (node (ref "JP6") (pin "11") (pinfunction "11_11") (pintype "passive"))
      (node (ref "RA6") (pin "P$11") (pinfunction "11_P$11") (pintype "passive"))
    )
    (net (code "97") (name "SOCK_NRD") (class "Default")
      (node (ref "JP6") (pin "7") (pinfunction "7_7") (pintype "passive"))
      (node (ref "RA7") (pin "P$11") (pinfunction "11_P$11") (pintype "passive"))
    )
    (net (code "98") (name "SOCK_NRST") (class "Default")
      (node (ref "JP6") (pin "8") (pinfunction "8_8") (pintype "passive"))
      (node (ref "RA7") (pin "P$22") (pinfunction "22_P$22") (pintype "passive"))
    )
    (net (code "99") (name "SOCK_NWR") (class "Default")
      (node (ref "JP6") (pin "13") (pinfunction "13_13") (pintype "passive"))
      (node (ref "RA6") (pin "P$33") (pinfunction "33_P$33") (pintype "passive"))
    )
    (net (code "100") (name "SOCK_ROTA") (class "Default")
      (node (ref "JP6") (pin "2") (pinfunction "2_2") (pintype "passive"))
      (node (ref "RA5") (pin "P$11") (pinfunction "11_P$11") (pintype "passive"))
    )
    (net (code "101") (name "SOCK_ROTB") (class "Default")
      (node (ref "JP6") (pin "4") (pinfunction "4_4") (pintype "passive"))
      (node (ref "RA5") (pin "P$33") (pinfunction "33_P$33") (pintype "passive"))
    )
    (net (code "102") (name "SOCK_ROTSW") (class "Default")
      (node (ref "JP6") (pin "1") (pinfunction "1_1") (pintype "passive"))
      (node (ref "RA5") (pin "P$22") (pinfunction "22_P$22") (pintype "passive"))
    )
    (net (code "103") (name "SPI_CLK") (class "Default")
      (node (ref "RA2") (pin "P$4") (pinfunction "4_P$4") (pintype "passive"))
      (node (ref "RA4") (pin "P$4") (pinfunction "4_P$4") (pintype "passive"))
      (node (ref "RA8") (pin "P$2") (pinfunction "2_P$2") (pintype "passive"))
      (node (ref "SPI") (pin "3") (pinfunction "3_3") (pintype "passive"))
      (node (ref "U$24") (pin "D5") (pinfunction "D5_D5") (pintype "bidirectional"))
      (node (ref "U23") (pin "21") (pinfunction "PA5_21") (pintype "bidirectional"))
    )
    (net (code "104") (name "SPI_MISO") (class "Default")
      (node (ref "RA2") (pin "P$3") (pinfunction "3_P$3") (pintype "passive"))
      (node (ref "RA4") (pin "P$3") (pinfunction "3_P$3") (pintype "passive"))
      (node (ref "U$24") (pin "D6") (pinfunction "D6_D6") (pintype "bidirectional"))
      (node (ref "U23") (pin "22") (pinfunction "PA6_22") (pintype "bidirectional"))
    )
    (net (code "105") (name "SPI_MOSI") (class "Default")
      (node (ref "RA2") (pin "P$2") (pinfunction "2_P$2") (pintype "passive"))
      (node (ref "RA4") (pin "P$2") (pinfunction "2_P$2") (pintype "passive"))
      (node (ref "RA8") (pin "P$4") (pinfunction "4_P$4") (pintype "passive"))
      (node (ref "SPI") (pin "1") (pinfunction "1_1") (pintype "passive"))
      (node (ref "U$24") (pin "D7") (pinfunction "D7_D7") (pintype "bidirectional"))
      (node (ref "U23") (pin "23") (pinfunction "PA7_23") (pintype "bidirectional"))
    )
    (net (code "106") (name "SWCLK") (class "Default")
      (node (ref "SWD1") (pin "2") (pinfunction "2_2") (pintype "passive"))
      (node (ref "U23") (pin "49") (pinfunction "PA14_49") (pintype "bidirectional"))
    )
    (net (code "107") (name "SWDIO") (class "Default")
      (node (ref "SWD1") (pin "4") (pinfunction "4_4") (pintype "passive"))
      (node (ref "U23") (pin "46") (pinfunction "PA13_46") (pintype "bidirectional"))
    )
    (net (code "108") (name "SWO") (class "Default")
      (node (ref "SWD1") (pin "6") (pinfunction "6_6") (pintype "passive"))
      (node (ref "U23") (pin "55") (pinfunction "PB3_55") (pintype "bidirectional"))
    )
    (net (code "109") (name "USB12V") (class "Default")
      (node (ref "D1") (pin "A") (pinfunction "A_A") (pintype "passive"))
      (node (ref "D2") (pin "C") (pinfunction "C_C") (pintype "passive"))
      (node (ref "LM317") (pin "3") (pinfunction "3_3") (pintype "passive"))
      (node (ref "R1") (pin "2") (pinfunction "2_2") (pintype "passive"))
      (node (ref "SJ3") (pin "1") (pinfunction "1_1") (pintype "passive"))
      (node (ref "SJ5") (pin "2") (pinfunction "2_2") (pintype "passive"))
      (node (ref "SJ6") (pin "2") (pinfunction "2_2") (pintype "passive"))
    )
    (net (code "110") (name "USBGND") (class "Default")
      (node (ref "C3") (pin "2") (pinfunction "2_2") (pintype "passive"))
      (node (ref "C4") (pin "2") (pinfunction "2_2") (pintype "passive"))
      (node (ref "H3") (pin "B3,2") (pinfunction "MOUNT_B3,2") (pintype "passive"))
      (node (ref "JP1") (pin "10") (pinfunction "10_10") (pintype "passive"))
      (node (ref "JP1") (pin "5") (pinfunction "5_5") (pintype "passive"))
      (node (ref "JP1") (pin "6") (pinfunction "6_6") (pintype "passive"))
      (node (ref "JP2") (pin "1") (pinfunction "1_1") (pintype "passive"))
      (node (ref "JP2") (pin "3") (pinfunction "3_3") (pintype "passive"))
      (node (ref "JP2") (pin "5") (pinfunction "5_5") (pintype "passive"))
      (node (ref "R2") (pin "1") (pinfunction "A_1") (pintype "passive"))
      (node (ref "SJ4") (pin "1") (pinfunction "1_1") (pintype "passive"))
    )
    (net (code "111") (name "USBVBUS") (class "Default")
      (node (ref "C3") (pin "1") (pinfunction "1_1") (pintype "passive"))
      (node (ref "D1") (pin "C") (pinfunction "C_C") (pintype "passive"))
      (node (ref "LM317") (pin "1") (pinfunction "1_1") (pintype "passive"))
      (node (ref "SJ12") (pin "1") (pinfunction "1_1") (pintype "passive"))
      (node (ref "SJ13") (pin "1") (pinfunction "1_1") (pintype "passive"))
      (node (ref "SJ14") (pin "1") (pinfunction "1_1") (pintype "passive"))
      (node (ref "SJ5") (pin "1") (pinfunction "1_1") (pintype "passive"))
      (node (ref "SJ6") (pin "1") (pinfunction "1_1") (pintype "passive"))
      (node (ref "SJ8") (pin "2") (pinfunction "2_2") (pintype "passive"))
      (node (ref "SJ9") (pin "2") (pinfunction "2_2") (pintype "passive"))
    )
    (net (code "112") (name "V3.3") (class "Default")
      (node (ref "C1") (pin "1") (pinfunction "1_1") (pintype "passive"))
      (node (ref "C10") (pin "1") (pinfunction "1_1") (pintype "passive"))
      (node (ref "C11") (pin "1") (pinfunction "1_1") (pintype "passive"))
      (node (ref "C14") (pin "1") (pinfunction "1_1") (pintype "passive"))
      (node (ref "C15") (pin "1") (pinfunction "1_1") (pintype "passive"))
      (node (ref "C16") (pin "1") (pinfunction "1_1") (pintype "passive"))
      (node (ref "C6") (pin "1") (pinfunction "1_1") (pintype "passive"))
      (node (ref "C7") (pin "1") (pinfunction "1_1") (pintype "passive"))
      (node (ref "C8") (pin "1") (pinfunction "1_1") (pintype "passive"))
      (node (ref "JP6") (pin "14") (pinfunction "14_14") (pintype "passive"))
      (node (ref "JP6") (pin "5") (pinfunction "5_5") (pintype "passive"))
      (node (ref "NFC0") (pin "1") (pinfunction "1_1") (pintype "passive"))
      (node (ref "NFC1") (pin "1") (pinfunction "1_1") (pintype "passive"))
      (node (ref "R10") (pin "1") (pinfunction "1_1") (pintype "passive"))
      (node (ref "R11") (pin "1") (pinfunction "1_1") (pintype "passive"))
      (node (ref "SJ10") (pin "2") (pinfunction "2_2") (pintype "passive"))
      (node (ref "SWD1") (pin "1") (pinfunction "1_1") (pintype "passive"))
      (node (ref "U$15") (pin "VOUT") (pinfunction "VO_VOUT") (pintype "output"))
      (node (ref "U$15") (pin "VOUTB") (pinfunction "BODY_VOUTB") (pintype "open_collector"))
      (node (ref "U$21") (pin "VCC") (pinfunction "VCC_VCC") (pintype "power_in"))
      (node (ref "U$22") (pin "VCC") (pinfunction "VCC_VCC") (pintype "power_in"))
      (node (ref "U$24") (pin "V3.3") (pinfunction "V3.3_V3.3") (pintype "bidirectional"))
      (node (ref "U$24") (pin "V3.3@1") (pinfunction "V3.3_V3.3@1") (pintype "bidirectional"))
      (node (ref "U$24") (pin "V3.3@2") (pinfunction "V3.3_V3.3@2") (pintype "bidirectional"))
      (node (ref "U1") (pin "23") (pinfunction "VCCB_2_23") (pintype "power_in"))
      (node (ref "U1") (pin "24") (pinfunction "VCCB_24") (pintype "power_in"))
      (node (ref "U23") (pin "1") (pinfunction "1:VBAT_1") (pintype "bidirectional"))
      (node (ref "U23") (pin "13") (pinfunction "13:VDDA_13") (pintype "bidirectional"))
      (node (ref "U23") (pin "19") (pinfunction "19:VDD_19") (pintype "bidirectional"))
      (node (ref "U23") (pin "32") (pinfunction "32:VDD_32") (pintype "bidirectional"))
      (node (ref "U23") (pin "48") (pinfunction "48:VDD_48") (pintype "bidirectional"))
      (node (ref "U23") (pin "64") (pinfunction "64:VDD_64") (pintype "bidirectional"))
    )
    (net (code "113") (name "V5") (class "Default")
      (node (ref "C5") (pin "1") (pinfunction "1_1") (pintype "passive"))
      (node (ref "C9") (pin "1") (pinfunction "1_1") (pintype "passive"))
      (node (ref "JP6") (pin "20") (pinfunction "20_20") (pintype "passive"))
      (node (ref "JP6") (pin "21") (pinfunction "21_21") (pintype "passive"))
      (node (ref "JP6") (pin "30") (pinfunction "30_30") (pintype "passive"))
      (node (ref "NFC0") (pin "9") (pinfunction "9_9") (pintype "passive"))
      (node (ref "NFC1") (pin "9") (pinfunction "9_9") (pintype "passive"))
      (node (ref "R12") (pin "1") (pinfunction "1_1") (pintype "passive"))
      (node (ref "SJ11") (pin "2") (pinfunction "2_2") (pintype "passive"))
      (node (ref "U$13") (pin "16") (pinfunction "VCC1_16") (pintype "bidirectional"))
      (node (ref "U$15") (pin "VIN") (pinfunction "VI_VIN") (pintype "input"))
      (node (ref "U$16") (pin "VO") (pinfunction "P$3_VO") (pintype "output"))
      (node (ref "U$24") (pin "V5") (pinfunction "V5_V5") (pintype "bidirectional"))
      (node (ref "U1") (pin "1") (pinfunction "VCCA_1") (pintype "power_in"))
    )
    (net (code "114") (name "V12") (class "Default")
      (node (ref "C2") (pin "1") (pinfunction "1_1") (pintype "passive"))
      (node (ref "J2") (pin "3") (pinfunction "3_3") (pintype "passive"))
      (node (ref "SJ3") (pin "2") (pinfunction "2_2") (pintype "passive"))
      (node (ref "U$13") (pin "8") (pinfunction "VCC2_8") (pintype "bidirectional"))
      (node (ref "U$16") (pin "VI") (pinfunction "P$1_VI") (pintype "input"))
    )
    (net (code "115") (name "VADJ") (class "Default")
      (node (ref "C4") (pin "1") (pinfunction "1_1") (pintype "passive"))
      (node (ref "D2") (pin "A") (pinfunction "A_A") (pintype "passive"))
      (node (ref "LM317") (pin "2") (pinfunction "2_2") (pintype "passive"))
      (node (ref "R1") (pin "1") (pinfunction "1_1") (pintype "passive"))
      (node (ref "R2") (pin "2") (pinfunction "S_2") (pintype "passive"))
    )
    (net (code "116") (name "VBUS") (class "Default")
      (node (ref "JP2") (pin "2") (pinfunction "2_2") (pintype "passive"))
      (node (ref "JP2") (pin "4") (pinfunction "4_4") (pintype "passive"))
      (node (ref "SJ12") (pin "2") (pinfunction "2_2") (pintype "passive"))
    )
    (net (code "117") (name "VBUS_A") (class "Default")
      (node (ref "JP1") (pin "4") (pinfunction "4_4") (pintype "passive"))
      (node (ref "SJ14") (pin "2") (pinfunction "2_2") (pintype "passive"))
    )
    (net (code "118") (name "VCAP") (class "Default")
      (node (ref "C12") (pin "1") (pinfunction "1_1") (pintype "passive"))
      (node (ref "U23") (pin "30") (pinfunction "30:VCAP_30") (pintype "bidirectional"))
    )
    (net (code "119") (name "VCONN") (class "Default")
      (node (ref "JP2") (pin "6") (pinfunction "6_6") (pintype "passive"))
      (node (ref "SJ13") (pin "2") (pinfunction "2_2") (pintype "passive"))
    )
    (net (code "120") (name "VCONNA") (class "Default")
      (node (ref "JP1") (pin "1") (pinfunction "1_1") (pintype "passive"))
      (node (ref "SJ9") (pin "1") (pinfunction "1_1") (pintype "passive"))
    )
    (net (code "121") (name "VDD") (class "Default")
      (node (ref "JP1") (pin "12") (pinfunction "12_12") (pintype "passive"))
      (node (ref "SJ8") (pin "1") (pinfunction "1_1") (pintype "passive"))
    )
    (net (code "122") (name "VLT_DIR") (class "Default")
      (node (ref "U1") (pin "2") (pinfunction "DIR_2") (pintype "input"))
      (node (ref "U23") (pin "36") (pinfunction "PB15_36") (pintype "bidirectional"))
    )
    (net (code "123") (name "VPU") (class "Default")
      (node (ref "JP1") (pin "11") (pinfunction "11_11") (pintype "passive"))
    )
    (net (code "124") (name "V_PULLUP") (class "Default")
      (node (ref "JP1") (pin "2") (pinfunction "2_2") (pintype "passive"))
    )
    (net (code "125") (name "WIFI_CS") (class "Default")
      (node (ref "U$24") (pin "D8") (pinfunction "D8_D8") (pintype "bidirectional"))
      (node (ref "U23") (pin "28") (pinfunction "PB2_28") (pintype "bidirectional"))
    )
    (net (code "126") (name "WIFI_GPIO") (class "Default")
      (node (ref "U$24") (pin "D1") (pinfunction "D1_D1") (pintype "bidirectional"))
    )
    (net (code "127") (name "WIFI_IRQ") (class "Default")
      (node (ref "U$24") (pin "D0") (pinfunction "D0_D0") (pintype "bidirectional"))
      (node (ref "U23") (pin "29") (pinfunction "PB10_29") (pintype "bidirectional"))
    )
    (net (code "128") (name "unconnected-(JP1-Pad3)") (class "Default")
      (node (ref "JP1") (pin "3") (pinfunction "3_3") (pintype "passive"))
    )
    (net (code "129") (name "unconnected-(JP6-Pad29)") (class "Default")
      (node (ref "JP6") (pin "29") (pinfunction "29_29") (pintype "passive"))
    )
    (net (code "130") (name "unconnected-(R2-E-Pad3)") (class "Default")
      (node (ref "R2") (pin "3") (pinfunction "E_3") (pintype "passive"))
    )
    (net (code "131") (name "unconnected-(RA0-4-PadP$4)") (class "Default")
      (node (ref "RA0") (pin "P$4") (pinfunction "4_P$4") (pintype "passive"))
    )
    (net (code "132") (name "unconnected-(RA0-44-PadP$44)") (class "Default")
      (node (ref "RA0") (pin "P$44") (pinfunction "44_P$44") (pintype "passive"))
    )
    (net (code "133") (name "unconnected-(RA1-1-PadP$1)") (class "Default")
      (node (ref "RA1") (pin "P$1") (pinfunction "1_P$1") (pintype "passive"))
    )
    (net (code "134") (name "unconnected-(RA1-2-PadP$2)") (class "Default")
      (node (ref "RA1") (pin "P$2") (pinfunction "2_P$2") (pintype "passive"))
    )
    (net (code "135") (name "unconnected-(RA1-11-PadP$11)") (class "Default")
      (node (ref "RA1") (pin "P$11") (pinfunction "11_P$11") (pintype "passive"))
    )
    (net (code "136") (name "unconnected-(RA1-22-PadP$22)") (class "Default")
      (node (ref "RA1") (pin "P$22") (pinfunction "22_P$22") (pintype "passive"))
    )
    (net (code "137") (name "unconnected-(RA3-1-PadP$1)") (class "Default")
      (node (ref "RA3") (pin "P$1") (pinfunction "1_P$1") (pintype "passive"))
    )
    (net (code "138") (name "unconnected-(RA3-2-PadP$2)") (class "Default")
      (node (ref "RA3") (pin "P$2") (pinfunction "2_P$2") (pintype "passive"))
    )
    (net (code "139") (name "unconnected-(RA3-11-PadP$11)") (class "Default")
      (node (ref "RA3") (pin "P$11") (pinfunction "11_P$11") (pintype "passive"))
    )
    (net (code "140") (name "unconnected-(RA3-22-PadP$22)") (class "Default")
      (node (ref "RA3") (pin "P$22") (pinfunction "22_P$22") (pintype "passive"))
    )
    (net (code "141") (name "unconnected-(RA6-4-PadP$4)") (class "Default")
      (node (ref "RA6") (pin "P$4") (pinfunction "4_P$4") (pintype "passive"))
    )
    (net (code "142") (name "unconnected-(RA6-44-PadP$44)") (class "Default")
      (node (ref "RA6") (pin "P$44") (pinfunction "44_P$44") (pintype "passive"))
    )
    (net (code "143") (name "unconnected-(RA9-4-PadP$4)") (class "Default")
      (node (ref "RA9") (pin "P$4") (pinfunction "4_P$4") (pintype "passive"))
    )
    (net (code "144") (name "unconnected-(RA9-44-PadP$44)") (class "Default")
      (node (ref "RA9") (pin "P$44") (pinfunction "44_P$44") (pintype "passive"))
    )
    (net (code "145") (name "unconnected-(U$1-CA-PadCATHODE)") (class "Default")
      (node (ref "U$1") (pin "CATHODE") (pinfunction "CA_CATHODE") (pintype "output"))
    )
    (net (code "146") (name "unconnected-(U$24-PadA0)") (class "Default")
      (node (ref "U$24") (pin "A0") (pinfunction "A0_A0") (pintype "bidirectional"))
    )
    (net (code "147") (name "unconnected-(U$24-PadCLK)") (class "Default")
      (node (ref "U$24") (pin "CLK") (pinfunction "CLK_CLK") (pintype "bidirectional"))
    )
    (net (code "148") (name "unconnected-(U$24-PadCMD)") (class "Default")
      (node (ref "U$24") (pin "CMD") (pinfunction "CMD_CMD") (pintype "bidirectional"))
    )
    (net (code "149") (name "unconnected-(U$24-PadD2)") (class "Default")
      (node (ref "U$24") (pin "D2") (pinfunction "D2_D2") (pintype "bidirectional"))
    )
    (net (code "150") (name "unconnected-(U$24-PadD3)") (class "Default")
      (node (ref "U$24") (pin "D3") (pinfunction "D3_D3") (pintype "bidirectional"))
    )
    (net (code "151") (name "unconnected-(U$24-PadD4)") (class "Default")
      (node (ref "U$24") (pin "D4") (pinfunction "D4_D4") (pintype "bidirectional"))
    )
    (net (code "152") (name "unconnected-(U$24-PadEN)") (class "Default")
      (node (ref "U$24") (pin "EN") (pinfunction "EN_EN") (pintype "bidirectional"))
    )
    (net (code "153") (name "unconnected-(U$24-PadRST)") (class "Default")
      (node (ref "U$24") (pin "RST") (pinfunction "RST_RST") (pintype "bidirectional"))
    )
    (net (code "154") (name "unconnected-(U$24-PadRSV)") (class "Default")
      (node (ref "U$24") (pin "RSV") (pinfunction "RSV_RSV") (pintype "bidirectional"))
    )
    (net (code "155") (name "unconnected-(U$24-PadRX)") (class "Default")
      (node (ref "U$24") (pin "RX") (pinfunction "RX_RX") (pintype "bidirectional"))
    )
    (net (code "156") (name "unconnected-(U$24-PadSD0)") (class "Default")
      (node (ref "U$24") (pin "SD0") (pinfunction "SD0_SD0") (pintype "bidirectional"))
    )
    (net (code "157") (name "unconnected-(U$24-PadSD1)") (class "Default")
      (node (ref "U$24") (pin "SD1") (pinfunction "SD1_SD1") (pintype "bidirectional"))
    )
    (net (code "158") (name "unconnected-(U$24-PadSD2)") (class "Default")
      (node (ref "U$24") (pin "SD2") (pinfunction "SD2_SD2") (pintype "bidirectional"))
    )
    (net (code "159") (name "unconnected-(U$24-PadSD3)") (class "Default")
      (node (ref "U$24") (pin "SD3") (pinfunction "SD3_SD3") (pintype "bidirectional"))
    )
    (net (code "160") (name "unconnected-(U$24-PadTX)") (class "Default")
      (node (ref "U$24") (pin "TX") (pinfunction "TX_TX") (pintype "bidirectional"))
    )
    (net (code "161") (name "unconnected-(U$24-RSV-PadRSV@1)") (class "Default")
      (node (ref "U$24") (pin "RSV@1") (pinfunction "RSV_RSV@1") (pintype "bidirectional"))
    )
    (net (code "162") (name "unconnected-(U1-A6-Pad9)") (class "Default")
      (node (ref "U1") (pin "9") (pinfunction "A6_9") (pintype "bidirectional"))
    )
    (net (code "163") (name "unconnected-(U1-A7-Pad10)") (class "Default")
      (node (ref "U1") (pin "10") (pinfunction "A7_10") (pintype "bidirectional"))
    )
    (net (code "164") (name "unconnected-(U1-B6-Pad15)") (class "Default")
      (node (ref "U1") (pin "15") (pinfunction "B6_15") (pintype "bidirectional"))
    )
    (net (code "165") (name "unconnected-(U1-B7-Pad14)") (class "Default")
      (node (ref "U1") (pin "14") (pinfunction "B7_14") (pintype "bidirectional"))
    )
    (net (code "166") (name "unconnected-(U2-Pad2)") (class "Default")
      (node (ref "U2") (pin "2") (pinfunction "2_2") (pintype "passive"))
    )
    (net (code "167") (name "unconnected-(U2-Pad4)") (class "Default")
      (node (ref "U2") (pin "4") (pinfunction "4_4") (pintype "passive"))
    )
  )
)
